# dynext_v2_1.net
KiCad netlist of a schematic drawn in EAGLE
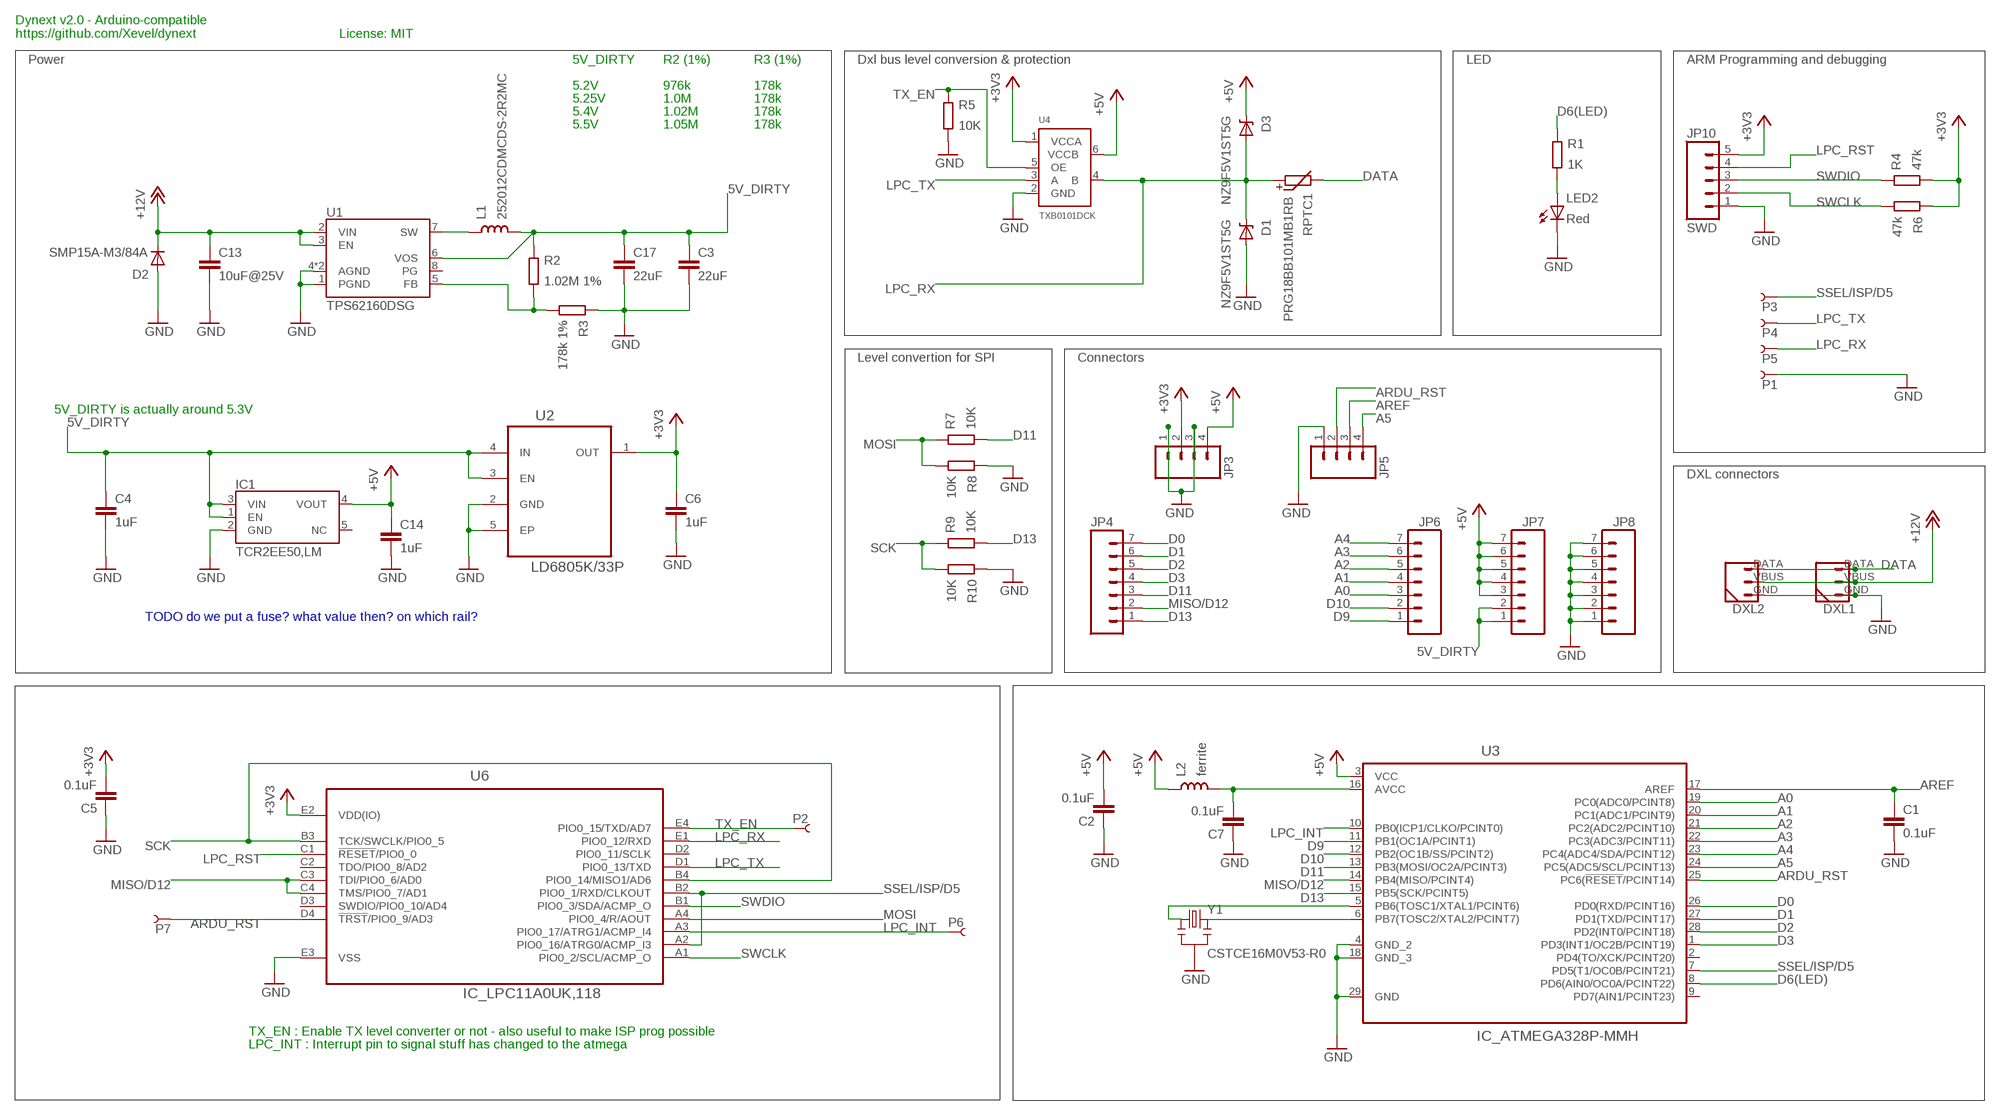
[diagram p0: schematic, sheet 1]

(export (version "E")
  (design (tool "Eeschema 10.0.6"))
  (components
    (comp (ref "C1")
      (value "0.1uF")
      (footprint "eagle-import:0201_N")
      (libsource (lib "eagle-import") (part "C0201"))
    )
    (comp (ref "C2")
      (value "0.1uF")
      (footprint "eagle-import:0201_N")
      (libsource (lib "eagle-import") (part "C0201"))
    )
    (comp (ref "C3")
      (value "22uF")
      (footprint "eagle-import:1206_N")
      (libsource (lib "eagle-import") (part "C1206"))
    )
    (comp (ref "C4")
      (value "1uF")
      (footprint "eagle-import:0402_N")
      (libsource (lib "eagle-import") (part "C0402"))
    )
    (comp (ref "C5")
      (value "0.1uF")
      (footprint "eagle-import:0201_N")
      (libsource (lib "eagle-import") (part "C0201"))
    )
    (comp (ref "C6")
      (value "1uF")
      (footprint "eagle-import:0402_N")
      (libsource (lib "eagle-import") (part "C0402"))
    )
    (comp (ref "C7")
      (value "0.1uF")
      (footprint "eagle-import:0201_N")
      (libsource (lib "eagle-import") (part "C0201"))
    )
    (comp (ref "C13")
      (value "10uF@25V")
      (footprint "eagle-import:0805_N")
      (libsource (lib "eagle-import") (part "C0805"))
    )
    (comp (ref "C14")
      (value "1uF")
      (footprint "eagle-import:0402_N")
      (libsource (lib "eagle-import") (part "C0402"))
    )
    (comp (ref "C17")
      (value "22uF")
      (footprint "eagle-import:1206_N")
      (libsource (lib "eagle-import") (part "C1206"))
    )
    (comp (ref "D1")
      (value "NZ9F5V1ST5G")
      (footprint "eagle-import:SOD-923_N")
      (libsource (lib "eagle-import") (part "DIODE_ZENER-923"))
    )
    (comp (ref "D2")
      (value "SMP15A-M3/84A")
      (footprint "eagle-import:DO-220AA")
      (libsource (lib "eagle-import") (part "DIODE-SMP"))
    )
    (comp (ref "D3")
      (value "NZ9F5V1ST5G")
      (footprint "eagle-import:SOD-923_N")
      (libsource (lib "eagle-import") (part "DIODE_ZENER-923"))
    )
    (comp (ref "DXL1")
      (value "DYNAMIXEL_3POS-R")
      (footprint "eagle-import:DYNAMIXEL_3POS_RIGHT")
      (libsource (lib "eagle-import") (part "DYNAMIXEL_3POS-R"))
    )
    (comp (ref "DXL2")
      (value "DYNAMIXEL_3POS-R")
      (footprint "eagle-import:DYNAMIXEL_3POS_RIGHT")
      (libsource (lib "eagle-import") (part "DYNAMIXEL_3POS-R"))
    )
    (comp (ref "IC1")
      (value "TCR2EE50,LM")
      (footprint "eagle-import:SOT50P160X60-5N")
      (libsource (lib "eagle-import") (part "IC_TCR2EEESV"))
    )
    (comp (ref "JP3")
      (value "M041X04_NO_SILK")
      (footprint "eagle-import:1X04_NO_SILK")
      (libsource (lib "eagle-import") (part "M041X04_NO_SILK"))
    )
    (comp (ref "JP4")
      (value "M07NO_SILK")
      (footprint "eagle-import:1X07_NO_SILK")
      (libsource (lib "eagle-import") (part "M07NO_SILK"))
    )
    (comp (ref "JP5")
      (value "M041X04_NO_SILK")
      (footprint "eagle-import:1X04_NO_SILK")
      (libsource (lib "eagle-import") (part "M041X04_NO_SILK"))
    )
    (comp (ref "JP6")
      (value "M07NO_SILK")
      (footprint "eagle-import:1X07_NO_SILK")
      (libsource (lib "eagle-import") (part "M07NO_SILK"))
    )
    (comp (ref "JP7")
      (value "M07NO_SILK")
      (footprint "eagle-import:1X07_NO_SILK")
      (libsource (lib "eagle-import") (part "M07NO_SILK"))
    )
    (comp (ref "JP8")
      (value "M07SQUARE_ALL")
      (footprint "eagle-import:1X07_SQUARE_ALL")
      (libsource (lib "eagle-import") (part "M07SQUARE_ALL"))
    )
    (comp (ref "JP10")
      (value "SWD")
      (footprint "eagle-import:1X05-1.27MM")
      (libsource (lib "eagle-import") (part "M051.27MM"))
    )
    (comp (ref "L1")
      (value "252012CDMCDS-2R2MC")
      (footprint "eagle-import:1008_N")
      (libsource (lib "eagle-import") (part "L1008"))
    )
    (comp (ref "L2")
      (value "ferrite")
      (footprint "eagle-import:0402_N")
      (libsource (lib "eagle-import") (part "L0402"))
    )
    (comp (ref "LED2")
      (value "Red")
      (footprint "eagle-import:D_0603_N")
      (libsource (lib "eagle-import") (part "LED0603"))
    )
    (comp (ref "P1")
      (value "PIN_SMD_0.8X2")
      (footprint "eagle-import:PIN_SMD_0.8X2")
      (libsource (lib "eagle-import") (part "PIN_SMD_0.8X2"))
    )
    (comp (ref "P2")
      (value "PIN_SMD_1X1")
      (footprint "eagle-import:PIN_SMD_1X1")
      (libsource (lib "eagle-import") (part "PIN_SMD_1X1"))
    )
    (comp (ref "P3")
      (value "PIN_SMD_0.8X2")
      (footprint "eagle-import:PIN_SMD_0.8X2")
      (libsource (lib "eagle-import") (part "PIN_SMD_0.8X2"))
    )
    (comp (ref "P4")
      (value "PIN_SMD_0.8X2")
      (footprint "eagle-import:PIN_SMD_0.8X2")
      (libsource (lib "eagle-import") (part "PIN_SMD_0.8X2"))
    )
    (comp (ref "P5")
      (value "PIN_SMD_0.8X2")
      (footprint "eagle-import:PIN_SMD_0.8X2")
      (libsource (lib "eagle-import") (part "PIN_SMD_0.8X2"))
    )
    (comp (ref "P6")
      (value "PIN_SMD_1X1")
      (footprint "eagle-import:PIN_SMD_1X1")
      (libsource (lib "eagle-import") (part "PIN_SMD_1X1"))
    )
    (comp (ref "P7")
      (value "PIN_SMD_1X1")
      (footprint "eagle-import:PIN_SMD_1X1")
      (libsource (lib "eagle-import") (part "PIN_SMD_1X1"))
    )
    (comp (ref "R1")
      (value "1K")
      (footprint "eagle-import:0201_N")
      (libsource (lib "eagle-import") (part "R0201"))
    )
    (comp (ref "R2")
      (value "1.02M 1%")
      (footprint "eagle-import:0201_N")
      (libsource (lib "eagle-import") (part "R0201"))
    )
    (comp (ref "R3")
      (value "178k 1%")
      (footprint "eagle-import:0201_N")
      (libsource (lib "eagle-import") (part "R0201"))
    )
    (comp (ref "R4")
      (value "47k")
      (footprint "eagle-import:0201_N")
      (libsource (lib "eagle-import") (part "R0201"))
    )
    (comp (ref "R5")
      (value "10K")
      (footprint "eagle-import:0201_N")
      (libsource (lib "eagle-import") (part "R0201"))
    )
    (comp (ref "R6")
      (value "47k")
      (footprint "eagle-import:0201_N")
      (libsource (lib "eagle-import") (part "R0201"))
    )
    (comp (ref "R7")
      (value "10K")
      (footprint "eagle-import:0201_N")
      (libsource (lib "eagle-import") (part "R0201"))
    )
    (comp (ref "R8")
      (value "10K")
      (footprint "eagle-import:0201_N")
      (libsource (lib "eagle-import") (part "R0201"))
    )
    (comp (ref "R9")
      (value "10K")
      (footprint "eagle-import:0201_N")
      (libsource (lib "eagle-import") (part "R0201"))
    )
    (comp (ref "R10")
      (value "10K")
      (footprint "eagle-import:0201_N")
      (libsource (lib "eagle-import") (part "R0201"))
    )
    (comp (ref "RPTC1")
      (value "PRG18BB101MB1RB")
      (footprint "eagle-import:0603_N")
      (libsource (lib "eagle-import") (part "R-PTC0603"))
    )
    (comp (ref "U1")
      (value "TPS62160DSG")
      (footprint "eagle-import:SON50P200X200X80-9L")
      (libsource (lib "eagle-import") (part "IC_TPS62160DSG_L"))
    )
    (comp (ref "U2")
      (value "LD6805K/33P")
      (footprint "eagle-import:NXP_LD6805")
      (libsource (lib "eagle-import") (part "LD6805K/33P"))
    )
    (comp (ref "U3")
      (value "IC_ATMEGA328P-MMH")
      (footprint "eagle-import:QFN45P400X400X100-29N")
      (fields (field (name "MPN") "ATMEGA328P-MMH"))
      (libsource (lib "eagle-import") (part "IC_ATMEGA328P-MMH"))
    )
    (comp (ref "U4")
      (value "TXB0101DCK")
      (footprint "eagle-import:SC70-6")
      (libsource (lib "eagle-import") (part "TXB0101DCK"))
    )
    (comp (ref "U6")
      (value "IC_LPC11A0UK,118")
      (footprint "eagle-import:BGA20C50P_250X250X65")
      (fields (field (name "MPN") "LPC11A02UK,118"))
      (libsource (lib "eagle-import") (part "IC_LPC11A0?UK,118"))
    )
    (comp (ref "Y1")
      (value "CSTCE16M0V53-R0")
      (footprint "eagle-import:RESONATOR-SMD")
      (libsource (lib "eagle-import") (part "RESONATOR16MHZ"))
    )
  )
  (nets
    (net (code "1") (name "+3V3") (class "Default")
      (node (ref "C5") (pin "2") (pinfunction "2_2") (pintype "passive"))
      (node (ref "C6") (pin "1") (pinfunction "1_1") (pintype "passive"))
      (node (ref "JP10") (pin "5") (pinfunction "5_5") (pintype "passive"))
      (node (ref "JP3") (pin "2") (pinfunction "2_2") (pintype "passive"))
      (node (ref "R4") (pin "1") (pinfunction "1_1") (pintype "passive"))
      (node (ref "R6") (pin "2") (pinfunction "2_2") (pintype "passive"))
      (node (ref "U2") (pin "1") (pinfunction "OUT_1") (pintype "power_in"))
      (node (ref "U4") (pin "1") (pinfunction "VCCA_1") (pintype "bidirectional"))
      (node (ref "U6") (pin "E2") (pinfunction "VDD(IO)_E2") (pintype "power_in"))
    )
    (net (code "2") (name "+5V") (class "Default")
      (node (ref "C14") (pin "1") (pinfunction "1_1") (pintype "passive"))
      (node (ref "C2") (pin "2") (pinfunction "2_2") (pintype "passive"))
      (node (ref "D3") (pin "C") (pinfunction "C_C") (pintype "passive"))
      (node (ref "IC1") (pin "4") (pinfunction "VOUT_4") (pintype "bidirectional"))
      (node (ref "JP3") (pin "4") (pinfunction "4_4") (pintype "passive"))
      (node (ref "JP7") (pin "3") (pinfunction "3_3") (pintype "passive"))
      (node (ref "JP7") (pin "4") (pinfunction "4_4") (pintype "passive"))
      (node (ref "JP7") (pin "5") (pinfunction "5_5") (pintype "passive"))
      (node (ref "JP7") (pin "6") (pinfunction "6_6") (pintype "passive"))
      (node (ref "JP7") (pin "7") (pinfunction "7_7") (pintype "passive"))
      (node (ref "L2") (pin "1") (pinfunction "1_1") (pintype "passive"))
      (node (ref "U3") (pin "3") (pinfunction "VCC_3") (pintype "power_in"))
      (node (ref "U4") (pin "6") (pinfunction "VCCB_6") (pintype "bidirectional"))
    )
    (net (code "3") (name "+12V") (class "Default")
      (node (ref "C13") (pin "1") (pinfunction "1_1") (pintype "passive"))
      (node (ref "D2") (pin "C") (pinfunction "C_C") (pintype "passive"))
      (node (ref "DXL1") (pin "VBUS") (pinfunction "2_VBUS") (pintype "bidirectional"))
      (node (ref "DXL2") (pin "VBUS") (pinfunction "2_VBUS") (pintype "bidirectional"))
      (node (ref "U1") (pin "2") (pinfunction "VIN_2") (pintype "bidirectional"))
      (node (ref "U1") (pin "3") (pinfunction "EN_3") (pintype "input"))
    )
    (net (code "4") (name "/5V_DIRTY") (class "Default")
      (node (ref "C17") (pin "1") (pinfunction "1_1") (pintype "passive"))
      (node (ref "C3") (pin "1") (pinfunction "1_1") (pintype "passive"))
      (node (ref "C4") (pin "1") (pinfunction "1_1") (pintype "passive"))
      (node (ref "IC1") (pin "1") (pinfunction "EN_1") (pintype "bidirectional"))
      (node (ref "IC1") (pin "3") (pinfunction "VIN_3") (pintype "bidirectional"))
      (node (ref "JP7") (pin "1") (pinfunction "1_1") (pintype "passive"))
      (node (ref "JP7") (pin "2") (pinfunction "2_2") (pintype "passive"))
      (node (ref "L1") (pin "2") (pinfunction "2_2") (pintype "passive"))
      (node (ref "R2") (pin "2") (pinfunction "2_2") (pintype "passive"))
      (node (ref "U1") (pin "6") (pinfunction "VOS_6") (pintype "bidirectional"))
      (node (ref "U2") (pin "3") (pinfunction "EN_3") (pintype "passive"))
      (node (ref "U2") (pin "4") (pinfunction "IN_4") (pintype "input"))
    )
    (net (code "5") (name "/A0") (class "Default")
      (node (ref "JP6") (pin "3") (pinfunction "3_3") (pintype "passive"))
      (node (ref "U3") (pin "19") (pinfunction "PC0(ADC0/PCINT8)_19") (pintype "bidirectional"))
    )
    (net (code "6") (name "/A1") (class "Default")
      (node (ref "JP6") (pin "4") (pinfunction "4_4") (pintype "passive"))
      (node (ref "U3") (pin "20") (pinfunction "PC1(ADC1/PCINT9)_20") (pintype "bidirectional"))
    )
    (net (code "7") (name "/A2") (class "Default")
      (node (ref "JP6") (pin "5") (pinfunction "5_5") (pintype "passive"))
      (node (ref "U3") (pin "21") (pinfunction "PC2(ADC2/PCINT10)_21") (pintype "bidirectional"))
    )
    (net (code "8") (name "/A3") (class "Default")
      (node (ref "JP6") (pin "6") (pinfunction "6_6") (pintype "passive"))
      (node (ref "U3") (pin "22") (pinfunction "PC3(ADC3/PCINT11)_22") (pintype "bidirectional"))
    )
    (net (code "9") (name "/A4") (class "Default")
      (node (ref "JP6") (pin "7") (pinfunction "7_7") (pintype "passive"))
      (node (ref "U3") (pin "23") (pinfunction "PC4(ADC4/SDA/PCINT12)_23") (pintype "bidirectional"))
    )
    (net (code "10") (name "/A5") (class "Default")
      (node (ref "JP5") (pin "4") (pinfunction "4_4") (pintype "passive"))
      (node (ref "U3") (pin "24") (pinfunction "PC5(ADC5/SCL/PCINT13)_24") (pintype "bidirectional"))
    )
    (net (code "11") (name "/ARDU_RST") (class "Default")
      (node (ref "JP5") (pin "2") (pinfunction "2_2") (pintype "passive"))
      (node (ref "P7") (pin "P$1") (pinfunction "1_P$1") (pintype "bidirectional"))
      (node (ref "U3") (pin "25") (pinfunction "PC6(~{RESET}/PCINT14)_25") (pintype "bidirectional"))
      (node (ref "U6") (pin "D4") (pinfunction "~{TRST}/PIO0_9/AD3_D4") (pintype "passive"))
    )
    (net (code "12") (name "/AREF") (class "Default")
      (node (ref "C1") (pin "1") (pinfunction "1_1") (pintype "passive"))
      (node (ref "JP5") (pin "3") (pinfunction "3_3") (pintype "passive"))
      (node (ref "U3") (pin "17") (pinfunction "AREF_17") (pintype "passive"))
    )
    (net (code "13") (name "/D0") (class "Default")
      (node (ref "JP4") (pin "7") (pinfunction "7_7") (pintype "passive"))
      (node (ref "U3") (pin "26") (pinfunction "PD0(RXD/PCINT16)_26") (pintype "bidirectional"))
    )
    (net (code "14") (name "/D1") (class "Default")
      (node (ref "JP4") (pin "6") (pinfunction "6_6") (pintype "passive"))
      (node (ref "U3") (pin "27") (pinfunction "PD1(TXD/PCINT17)_27") (pintype "bidirectional"))
    )
    (net (code "15") (name "/D2") (class "Default")
      (node (ref "JP4") (pin "5") (pinfunction "5_5") (pintype "passive"))
      (node (ref "U3") (pin "28") (pinfunction "PD2(INT0/PCINT18)_28") (pintype "bidirectional"))
    )
    (net (code "16") (name "/D3") (class "Default")
      (node (ref "JP4") (pin "4") (pinfunction "4_4") (pintype "passive"))
      (node (ref "U3") (pin "1") (pinfunction "PD3(INT1/OC2B/PCINT19)_1") (pintype "bidirectional"))
    )
    (net (code "17") (name "/D6(LED)") (class "Default")
      (node (ref "R1") (pin "2") (pinfunction "2_2") (pintype "passive"))
      (node (ref "U3") (pin "8") (pinfunction "PD6(AIN0/OC0A/PCINT22)_8") (pintype "bidirectional"))
    )
    (net (code "18") (name "/D9") (class "Default")
      (node (ref "JP6") (pin "1") (pinfunction "1_1") (pintype "passive"))
      (node (ref "U3") (pin "11") (pinfunction "PB1(OC1A/PCINT1)_11") (pintype "bidirectional"))
    )
    (net (code "19") (name "/D10") (class "Default")
      (node (ref "JP6") (pin "2") (pinfunction "2_2") (pintype "passive"))
      (node (ref "U3") (pin "12") (pinfunction "PB2(OC1B/SS/PCINT2)_12") (pintype "bidirectional"))
    )
    (net (code "20") (name "/D11") (class "Default")
      (node (ref "JP4") (pin "3") (pinfunction "3_3") (pintype "passive"))
      (node (ref "R7") (pin "1") (pinfunction "1_1") (pintype "passive"))
      (node (ref "U3") (pin "13") (pinfunction "PB3(MOSI/OC2A/PCINT3)_13") (pintype "bidirectional"))
    )
    (net (code "21") (name "/D13") (class "Default")
      (node (ref "JP4") (pin "1") (pinfunction "1_1") (pintype "passive"))
      (node (ref "R9") (pin "1") (pinfunction "1_1") (pintype "passive"))
      (node (ref "U3") (pin "15") (pinfunction "PB5(SCK/PCINT5)_15") (pintype "bidirectional"))
    )
    (net (code "22") (name "/DATA") (class "Default")
      (node (ref "DXL1") (pin "DATA") (pinfunction "3_DATA") (pintype "bidirectional"))
      (node (ref "DXL2") (pin "DATA") (pinfunction "3_DATA") (pintype "bidirectional"))
      (node (ref "RPTC1") (pin "2") (pinfunction "2_2") (pintype "passive"))
    )
    (net (code "23") (name "/LPC_INT") (class "Default")
      (node (ref "P6") (pin "P$1") (pinfunction "1_P$1") (pintype "bidirectional"))
      (node (ref "U3") (pin "10") (pinfunction "PB0(ICP1/CLKO/PCINT0)_10") (pintype "bidirectional"))
      (node (ref "U6") (pin "A3") (pinfunction "PIO0_17/ATRG1/ACMP_I4_A3") (pintype "bidirectional"))
    )
    (net (code "24") (name "/LPC_RST") (class "Default")
      (node (ref "JP10") (pin "4") (pinfunction "4_4") (pintype "passive"))
      (node (ref "U6") (pin "C1") (pinfunction "~{RESET}/PIO0_0_C1") (pintype "passive"))
    )
    (net (code "25") (name "/LPC_RX") (class "Default")
      (node (ref "D1") (pin "C") (pinfunction "C_C") (pintype "passive"))
      (node (ref "D3") (pin "A") (pinfunction "A_A") (pintype "passive"))
      (node (ref "P5") (pin "PIN") (pinfunction "1_PIN") (pintype "bidirectional"))
      (node (ref "RPTC1") (pin "1") (pinfunction "1_1") (pintype "passive"))
      (node (ref "U4") (pin "4") (pinfunction "B_4") (pintype "bidirectional"))
      (node (ref "U6") (pin "E1") (pinfunction "PIO0_12/RXD_E1") (pintype "bidirectional"))
    )
    (net (code "26") (name "/LPC_TX") (class "Default")
      (node (ref "P4") (pin "PIN") (pinfunction "1_PIN") (pintype "bidirectional"))
      (node (ref "U4") (pin "3") (pinfunction "A_3") (pintype "bidirectional"))
      (node (ref "U6") (pin "D1") (pinfunction "PIO0_13/TXD_D1") (pintype "bidirectional"))
    )
    (net (code "27") (name "/MISO{slash}D12") (class "Default")
      (node (ref "JP4") (pin "2") (pinfunction "2_2") (pintype "passive"))
      (node (ref "U3") (pin "14") (pinfunction "PB4(MISO/PCINT4)_14") (pintype "bidirectional"))
      (node (ref "U6") (pin "C3") (pinfunction "TDI/PIO0_6/AD0_C3") (pintype "passive"))
      (node (ref "U6") (pin "C4") (pinfunction "TMS/PIO0_7/AD1_C4") (pintype "passive"))
    )
    (net (code "28") (name "/MOSI") (class "Default")
      (node (ref "R7") (pin "2") (pinfunction "2_2") (pintype "passive"))
      (node (ref "R8") (pin "1") (pinfunction "1_1") (pintype "passive"))
      (node (ref "U6") (pin "A4") (pinfunction "PIO0_4/R/AOUT_A4") (pintype "bidirectional"))
    )
    (net (code "29") (name "/SCK") (class "Default")
      (node (ref "R10") (pin "1") (pinfunction "1_1") (pintype "passive"))
      (node (ref "R9") (pin "2") (pinfunction "2_2") (pintype "passive"))
      (node (ref "U6") (pin "B3") (pinfunction "TCK/SWCLK/PIO0_5_B3") (pintype "passive"))
      (node (ref "U6") (pin "B4") (pinfunction "PIO0_14/MISO1/AD6_B4") (pintype "bidirectional"))
    )
    (net (code "30") (name "/SSEL{slash}ISP{slash}D5") (class "Default")
      (node (ref "P3") (pin "PIN") (pinfunction "1_PIN") (pintype "bidirectional"))
      (node (ref "U3") (pin "7") (pinfunction "PD5(T1/OC0B/PCINT21)_7") (pintype "bidirectional"))
      (node (ref "U6") (pin "A2") (pinfunction "PIO0_16/ATRG0/ACMP_I3_A2") (pintype "bidirectional"))
      (node (ref "U6") (pin "B2") (pinfunction "PIO0_1/RXD/CLKOUT_B2") (pintype "bidirectional"))
    )
    (net (code "31") (name "/SWCLK") (class "Default")
      (node (ref "JP10") (pin "2") (pinfunction "2_2") (pintype "passive"))
      (node (ref "R6") (pin "1") (pinfunction "1_1") (pintype "passive"))
      (node (ref "U6") (pin "A1") (pinfunction "PIO0_2/SCL/ACMP_O_A1") (pintype "bidirectional"))
    )
    (net (code "32") (name "/SWDIO") (class "Default")
      (node (ref "JP10") (pin "3") (pinfunction "3_3") (pintype "passive"))
      (node (ref "R4") (pin "2") (pinfunction "2_2") (pintype "passive"))
      (node (ref "U6") (pin "B1") (pinfunction "PIO0_3/SDA/ACMP_O_B1") (pintype "bidirectional"))
    )
    (net (code "33") (name "/TX_EN") (class "Default")
      (node (ref "P2") (pin "P$1") (pinfunction "1_P$1") (pintype "bidirectional"))
      (node (ref "R5") (pin "2") (pinfunction "2_2") (pintype "passive"))
      (node (ref "U4") (pin "5") (pinfunction "OE_5") (pintype "bidirectional"))
      (node (ref "U6") (pin "E4") (pinfunction "PIO0_15/TXD/AD7_E4") (pintype "bidirectional"))
    )
    (net (code "34") (name "GND") (class "Default")
      (node (ref "C1") (pin "2") (pinfunction "2_2") (pintype "passive"))
      (node (ref "C13") (pin "2") (pinfunction "2_2") (pintype "passive"))
      (node (ref "C14") (pin "2") (pinfunction "2_2") (pintype "passive"))
      (node (ref "C17") (pin "2") (pinfunction "2_2") (pintype "passive"))
      (node (ref "C2") (pin "1") (pinfunction "1_1") (pintype "passive"))
      (node (ref "C3") (pin "2") (pinfunction "2_2") (pintype "passive"))
      (node (ref "C4") (pin "2") (pinfunction "2_2") (pintype "passive"))
      (node (ref "C5") (pin "1") (pinfunction "1_1") (pintype "passive"))
      (node (ref "C6") (pin "2") (pinfunction "2_2") (pintype "passive"))
      (node (ref "C7") (pin "1") (pinfunction "1_1") (pintype "passive"))
      (node (ref "D1") (pin "A") (pinfunction "A_A") (pintype "passive"))
      (node (ref "D2") (pin "A") (pinfunction "A_A") (pintype "passive"))
      (node (ref "DXL1") (pin "GND") (pinfunction "1_GND") (pintype "bidirectional"))
      (node (ref "DXL2") (pin "GND") (pinfunction "1_GND") (pintype "bidirectional"))
      (node (ref "IC1") (pin "2") (pinfunction "GND_2") (pintype "power_in"))
      (node (ref "JP10") (pin "1") (pinfunction "1_1") (pintype "passive"))
      (node (ref "JP3") (pin "1") (pinfunction "1_1") (pintype "passive"))
      (node (ref "JP3") (pin "3") (pinfunction "3_3") (pintype "passive"))
      (node (ref "JP5") (pin "1") (pinfunction "1_1") (pintype "passive"))
      (node (ref "JP8") (pin "1") (pinfunction "1_1") (pintype "passive"))
      (node (ref "JP8") (pin "2") (pinfunction "2_2") (pintype "passive"))
      (node (ref "JP8") (pin "3") (pinfunction "3_3") (pintype "passive"))
      (node (ref "JP8") (pin "4") (pinfunction "4_4") (pintype "passive"))
      (node (ref "JP8") (pin "5") (pinfunction "5_5") (pintype "passive"))
      (node (ref "JP8") (pin "6") (pinfunction "6_6") (pintype "passive"))
      (node (ref "JP8") (pin "7") (pinfunction "7_7") (pintype "passive"))
      (node (ref "LED2") (pin "C") (pinfunction "C_C") (pintype "passive"))
      (node (ref "P1") (pin "PIN") (pinfunction "1_PIN") (pintype "bidirectional"))
      (node (ref "R10") (pin "2") (pinfunction "2_2") (pintype "passive"))
      (node (ref "R3") (pin "2") (pinfunction "2_2") (pintype "passive"))
      (node (ref "R5") (pin "1") (pinfunction "1_1") (pintype "passive"))
      (node (ref "R8") (pin "2") (pinfunction "2_2") (pintype "passive"))
      (node (ref "U1") (pin "1") (pinfunction "PGND_1") (pintype "input"))
      (node (ref "U1") (pin "4") (pinfunction "AGND_4") (pintype "input"))
      (node (ref "U1") (pin "9") (pinfunction "AGND_9") (pintype "input"))
      (node (ref "U2") (pin "2") (pinfunction "GND_2") (pintype "power_in"))
      (node (ref "U2") (pin "5") (pinfunction "EP_5") (pintype "passive"))
      (node (ref "U3") (pin "18") (pinfunction "GND_3_18") (pintype "power_in"))
      (node (ref "U3") (pin "29") (pinfunction "GND_29") (pintype "power_in"))
      (node (ref "U3") (pin "4") (pinfunction "GND_2_4") (pintype "power_in"))
      (node (ref "U4") (pin "2") (pinfunction "GND_2") (pintype "bidirectional"))
      (node (ref "U6") (pin "E3") (pinfunction "VSS_E3") (pintype "power_in"))
      (node (ref "Y1") (pin "2") (pinfunction "2_2") (pintype "passive"))
    )
    (net (code "35") (name "Net-(LED2-PadA)") (class "Default")
      (node (ref "LED2") (pin "A") (pinfunction "A_A") (pintype "passive"))
      (node (ref "R1") (pin "1") (pinfunction "1_1") (pintype "passive"))
    )
    (net (code "36") (name "Net-(U1-FB)") (class "Default")
      (node (ref "R2") (pin "1") (pinfunction "1_1") (pintype "passive"))
      (node (ref "R3") (pin "1") (pinfunction "1_1") (pintype "passive"))
      (node (ref "U1") (pin "5") (pinfunction "FB_5") (pintype "bidirectional"))
    )
    (net (code "37") (name "Net-(U1-SW)") (class "Default")
      (node (ref "L1") (pin "1") (pinfunction "1_1") (pintype "passive"))
      (node (ref "U1") (pin "7") (pinfunction "SW_7") (pintype "bidirectional"))
    )
    (net (code "38") (name "Net-(U3-AVCC)") (class "Default")
      (node (ref "C7") (pin "2") (pinfunction "2_2") (pintype "passive"))
      (node (ref "L2") (pin "2") (pinfunction "2_2") (pintype "passive"))
      (node (ref "U3") (pin "16") (pinfunction "AVCC_16") (pintype "power_in"))
    )
    (net (code "39") (name "Net-(U3-PB6(TOSC1{slash}XTAL1{slash}PCINT6))") (class "Default")
      (node (ref "U3") (pin "5") (pinfunction "PB6(TOSC1/XTAL1/PCINT6)_5") (pintype "bidirectional"))
      (node (ref "Y1") (pin "1") (pinfunction "1_1") (pintype "passive"))
    )
    (net (code "40") (name "Net-(U3-PB7(TOSC2{slash}XTAL2{slash}PCINT7))") (class "Default")
      (node (ref "U3") (pin "6") (pinfunction "PB7(TOSC2/XTAL2/PCINT7)_6") (pintype "bidirectional"))
      (node (ref "Y1") (pin "3") (pinfunction "3_3") (pintype "passive"))
    )
    (net (code "41") (name "unconnected-(IC1-NC-Pad5)") (class "Default")
      (node (ref "IC1") (pin "5") (pinfunction "NC_5") (pintype "no_connect"))
    )
    (net (code "42") (name "unconnected-(U1-PG-Pad8)") (class "Default")
      (node (ref "U1") (pin "8") (pinfunction "PG_8") (pintype "bidirectional"))
    )
    (net (code "43") (name "unconnected-(U3-PD4(TO{slash}XCK{slash}PCINT20)-Pad2)") (class "Default")
      (node (ref "U3") (pin "2") (pinfunction "PD4(TO/XCK/PCINT20)_2") (pintype "bidirectional"))
    )
    (net (code "44") (name "unconnected-(U3-PD7(AIN1{slash}PCINT23)-Pad9)") (class "Default")
      (node (ref "U3") (pin "9") (pinfunction "PD7(AIN1/PCINT23)_9") (pintype "bidirectional"))
    )
    (net (code "45") (name "unconnected-(U6-PIO0_11{slash}SCLK-PadD2)") (class "Default")
      (node (ref "U6") (pin "D2") (pinfunction "PIO0_11/SCLK_D2") (pintype "bidirectional"))
    )
    (net (code "46") (name "unconnected-(U6-SWDIO{slash}PIO0_10{slash}AD4-PadD3)") (class "Default")
      (node (ref "U6") (pin "D3") (pinfunction "SWDIO/PIO0_10/AD4_D3") (pintype "passive"))
    )
    (net (code "47") (name "unconnected-(U6-TDO{slash}PIO0_8{slash}AD2-PadC2)") (class "Default")
      (node (ref "U6") (pin "C2") (pinfunction "TDO/PIO0_8/AD2_C2") (pintype "passive"))
    )
  )
)
